# 85veegashield_v2.net
KiCad netlist of a schematic drawn in EAGLE
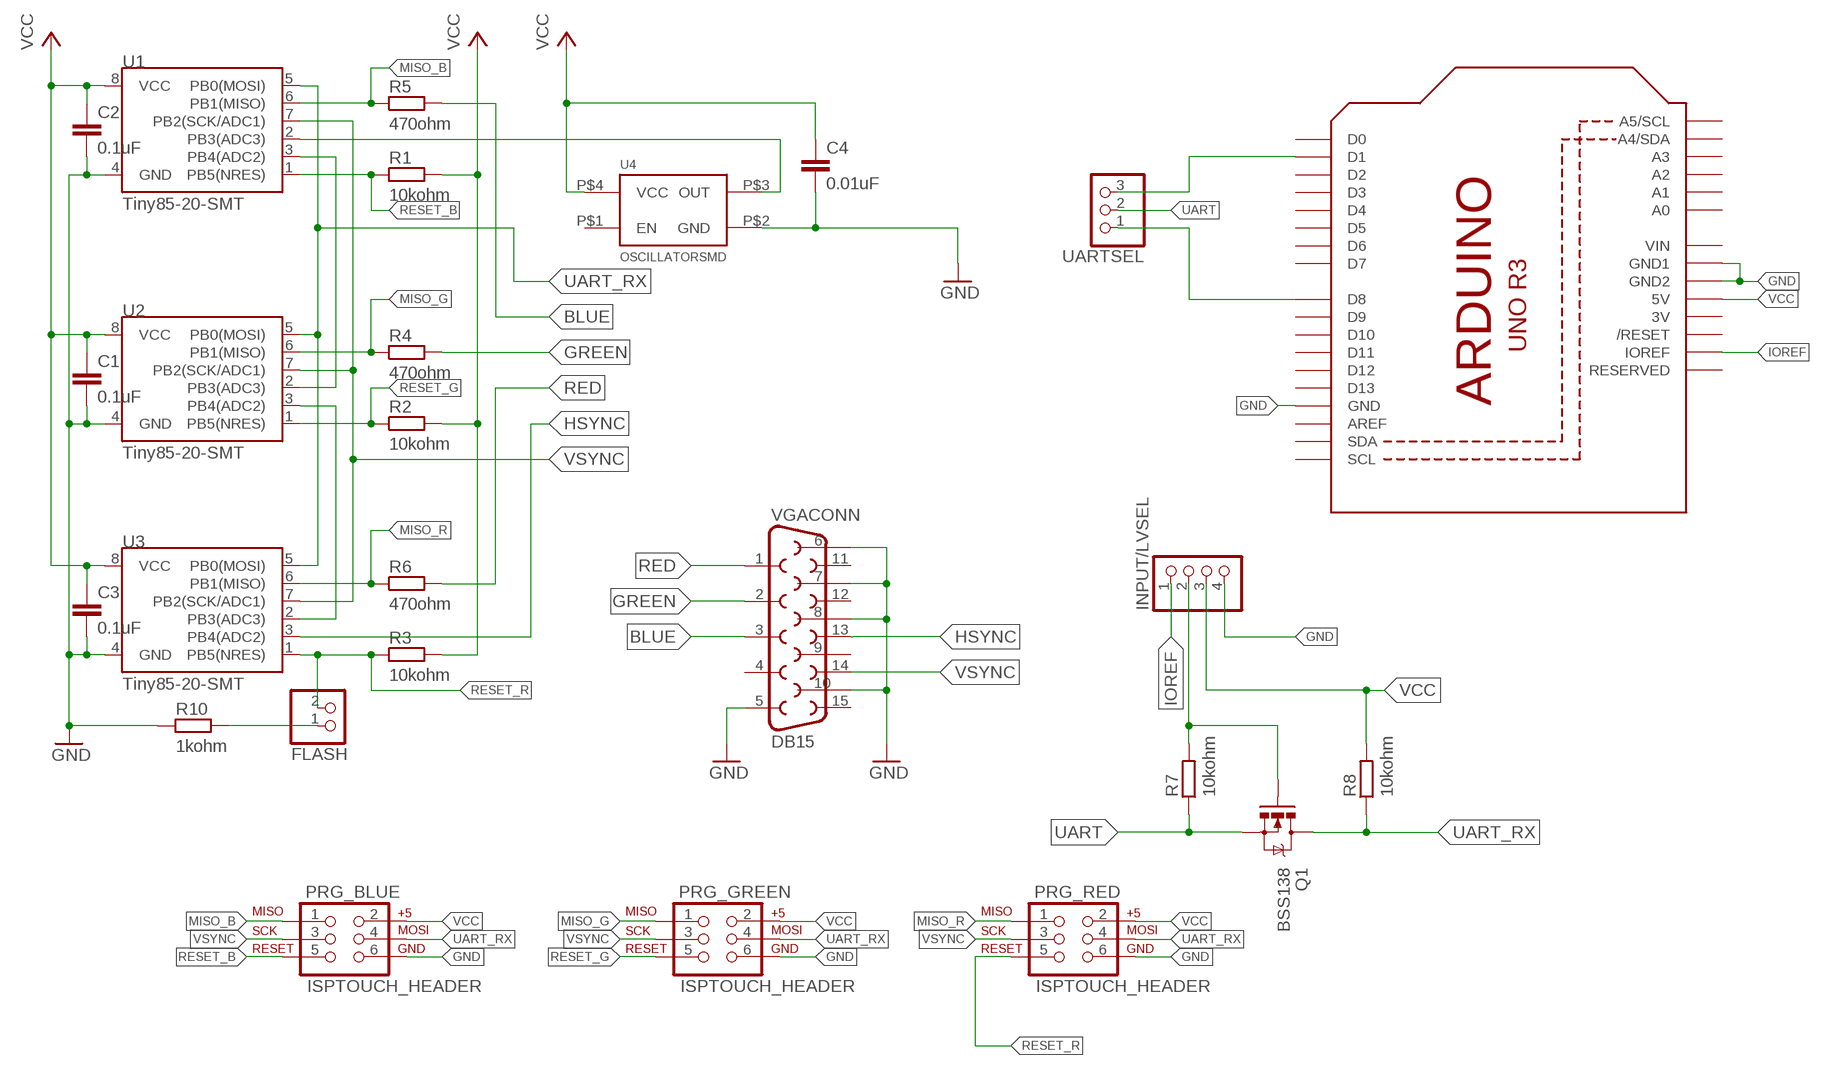
[diagram p0: schematic, sheet 1]

(export (version "E")
  (design (tool "Eeschema 10.0.6"))
  (components
    (comp (ref "C1")
      (value "0.1uF")
      (footprint "eagle-import:0603-CAP")
      (libsource (lib "eagle-import") (part "CAP0603-CAP"))
    )
    (comp (ref "C2")
      (value "0.1uF")
      (footprint "eagle-import:0603-CAP")
      (libsource (lib "eagle-import") (part "CAP0603-CAP"))
    )
    (comp (ref "C3")
      (value "0.1uF")
      (footprint "eagle-import:0603-CAP")
      (libsource (lib "eagle-import") (part "CAP0603-CAP"))
    )
    (comp (ref "C4")
      (value "0.01uF")
      (footprint "eagle-import:0603-CAP")
      (libsource (lib "eagle-import") (part "CAP0603-CAP"))
    )
    (comp (ref "FLASH")
      (value "PINHD-1X02_2.54-S")
      (footprint "eagle-import:1X02-S")
      (libsource (lib "eagle-import") (part "PINHD-1X02_2.54-S"))
    )
    (comp (ref "INPUT/LVSEL")
      (value "PINHD-1X04_2.54-S")
      (footprint "eagle-import:1X04-S")
      (libsource (lib "eagle-import") (part "PINHD-1X04_2.54-S"))
    )
    (comp (ref "PRG_BLUE")
      (value "ISPTOUCH_HEADER")
      (footprint "eagle-import:AVX_9188_6-WAY_MATING_GUIDE")
      (libsource (lib "eagle-import") (part "ISPTOUCH_HEADER"))
    )
    (comp (ref "PRG_GREEN")
      (value "ISPTOUCH_HEADER")
      (footprint "eagle-import:AVX_9188_6-WAY_MATING_GUIDE")
      (libsource (lib "eagle-import") (part "ISPTOUCH_HEADER"))
    )
    (comp (ref "PRG_RED")
      (value "ISPTOUCH_HEADER")
      (footprint "eagle-import:AVX_9188_6-WAY_MATING_GUIDE")
      (libsource (lib "eagle-import") (part "ISPTOUCH_HEADER"))
    )
    (comp (ref "Q1")
      (value "BSS138")
      (footprint "eagle-import:SOT23")
      (libsource (lib "eagle-import") (part "MOSFET-NCHANNELBSS138"))
    )
    (comp (ref "R1")
      (value "10kohm")
      (footprint "eagle-import:R0603")
      (libsource (lib "eagle-import") (part "RESISTOR"))
    )
    (comp (ref "R2")
      (value "10kohm")
      (footprint "eagle-import:R0603")
      (libsource (lib "eagle-import") (part "RESISTOR"))
    )
    (comp (ref "R3")
      (value "10kohm")
      (footprint "eagle-import:R0603")
      (libsource (lib "eagle-import") (part "RESISTOR"))
    )
    (comp (ref "R4")
      (value "470ohm")
      (footprint "eagle-import:R0603")
      (libsource (lib "eagle-import") (part "RESISTOR"))
    )
    (comp (ref "R5")
      (value "470ohm")
      (footprint "eagle-import:R0603")
      (libsource (lib "eagle-import") (part "RESISTOR"))
    )
    (comp (ref "R6")
      (value "470ohm")
      (footprint "eagle-import:R0603")
      (libsource (lib "eagle-import") (part "RESISTOR"))
    )
    (comp (ref "R7")
      (value "10kohm")
      (footprint "eagle-import:R0603")
      (libsource (lib "eagle-import") (part "RESISTOR"))
    )
    (comp (ref "R8")
      (value "10kohm")
      (footprint "eagle-import:R0603")
      (libsource (lib "eagle-import") (part "RESISTOR"))
    )
    (comp (ref "R10")
      (value "1kohm")
      (footprint "eagle-import:R0603")
      (libsource (lib "eagle-import") (part "RESISTOR"))
    )
    (comp (ref "U$1")
      (value "ARDUINOR3-DIMENSION")
      (footprint "eagle-import:ARDUINOR3")
      (libsource (lib "eagle-import") (part "ARDUINOR3-DIMENSION"))
    )
    (comp (ref "U1")
      (value "Tiny85-20-SMT")
      (footprint "eagle-import:SO08-EIAJ")
      (libsource (lib "eagle-import") (part "ATTINY45TINY85-20-SMT"))
    )
    (comp (ref "U2")
      (value "Tiny85-20-SMT")
      (footprint "eagle-import:SO08-EIAJ")
      (libsource (lib "eagle-import") (part "ATTINY45TINY85-20-SMT"))
    )
    (comp (ref "U3")
      (value "Tiny85-20-SMT")
      (footprint "eagle-import:SO08-EIAJ")
      (libsource (lib "eagle-import") (part "ATTINY45TINY85-20-SMT"))
    )
    (comp (ref "U4")
      (value "OSCILLATORSMD")
      (footprint "eagle-import:CRYSTAL-SMD-7X5")
      (libsource (lib "eagle-import") (part "OSCILLATORSMD"))
    )
    (comp (ref "UARTSEL")
      (value "PINHD-1X03_2.54-S")
      (footprint "eagle-import:1X03-S")
      (libsource (lib "eagle-import") (part "PINHD-1X03_2.54-S"))
    )
    (comp (ref "VGACONN")
      (value "DB15")
      (footprint "eagle-import:DB15")
      (libsource (lib "eagle-import") (part "DB15"))
    )
  )
  (nets
    (net (code "1") (name "/3V") (class "Default")
      (node (ref "U$1") (pin "3V") (pinfunction "3V_3V") (pintype "power_in"))
    )
    (net (code "2") (name "/VIN") (class "Default")
      (node (ref "U$1") (pin "VIN") (pinfunction "VIN_VIN") (pintype "power_in"))
    )
    (net (code "3") (name "BLUE") (class "Default")
      (node (ref "R5") (pin "2") (pinfunction "2_2") (pintype "passive"))
      (node (ref "VGACONN") (pin "3") (pinfunction "3_3") (pintype "passive"))
    )
    (net (code "4") (name "GND") (class "Default")
      (node (ref "C1") (pin "2") (pinfunction "2_2") (pintype "passive"))
      (node (ref "C2") (pin "2") (pinfunction "2_2") (pintype "passive"))
      (node (ref "C3") (pin "2") (pinfunction "2_2") (pintype "passive"))
      (node (ref "C4") (pin "2") (pinfunction "2_2") (pintype "passive"))
      (node (ref "INPUT/LVSEL") (pin "4") (pinfunction "4_4") (pintype "passive"))
      (node (ref "PRG_BLUE") (pin "6") (pinfunction "6_6") (pintype "passive"))
      (node (ref "PRG_GREEN") (pin "6") (pinfunction "6_6") (pintype "passive"))
      (node (ref "PRG_RED") (pin "6") (pinfunction "6_6") (pintype "passive"))
      (node (ref "R10") (pin "1") (pinfunction "1_1") (pintype "passive"))
      (node (ref "U$1") (pin "GND") (pinfunction "GND_GND") (pintype "power_in"))
      (node (ref "U$1") (pin "GND1") (pinfunction "GND1_GND1") (pintype "power_in"))
      (node (ref "U$1") (pin "GND2") (pinfunction "GND2_GND2") (pintype "power_in"))
      (node (ref "U1") (pin "4") (pinfunction "GND_4") (pintype "bidirectional"))
      (node (ref "U2") (pin "4") (pinfunction "GND_4") (pintype "bidirectional"))
      (node (ref "U3") (pin "4") (pinfunction "GND_4") (pintype "bidirectional"))
      (node (ref "U4") (pin "P$2") (pinfunction "GND_P$2") (pintype "bidirectional"))
      (node (ref "VGACONN") (pin "10") (pinfunction "10_10") (pintype "passive"))
      (node (ref "VGACONN") (pin "5") (pinfunction "5_5") (pintype "passive"))
      (node (ref "VGACONN") (pin "6") (pinfunction "6_6") (pintype "passive"))
      (node (ref "VGACONN") (pin "7") (pinfunction "7_7") (pintype "passive"))
      (node (ref "VGACONN") (pin "8") (pinfunction "8_8") (pintype "passive"))
    )
    (net (code "5") (name "GREEN") (class "Default")
      (node (ref "R4") (pin "2") (pinfunction "2_2") (pintype "passive"))
      (node (ref "VGACONN") (pin "2") (pinfunction "2_2") (pintype "passive"))
    )
    (net (code "6") (name "HSYNC") (class "Default")
      (node (ref "U3") (pin "3") (pinfunction "PB4(ADC2)_3") (pintype "bidirectional"))
      (node (ref "VGACONN") (pin "13") (pinfunction "13_13") (pintype "passive"))
    )
    (net (code "7") (name "IOREF") (class "Default")
      (node (ref "INPUT/LVSEL") (pin "1") (pinfunction "1_1") (pintype "passive"))
      (node (ref "U$1") (pin "IOREF") (pinfunction "IOREF_IOREF") (pintype "output"))
    )
    (net (code "8") (name "MISO_B") (class "Default")
      (node (ref "PRG_BLUE") (pin "1") (pinfunction "1_1") (pintype "passive"))
      (node (ref "R5") (pin "1") (pinfunction "1_1") (pintype "passive"))
      (node (ref "U1") (pin "6") (pinfunction "PB1(MISO)_6") (pintype "bidirectional"))
    )
    (net (code "9") (name "MISO_G") (class "Default")
      (node (ref "PRG_GREEN") (pin "1") (pinfunction "1_1") (pintype "passive"))
      (node (ref "R4") (pin "1") (pinfunction "1_1") (pintype "passive"))
      (node (ref "U2") (pin "6") (pinfunction "PB1(MISO)_6") (pintype "bidirectional"))
    )
    (net (code "10") (name "MISO_R") (class "Default")
      (node (ref "PRG_RED") (pin "1") (pinfunction "1_1") (pintype "passive"))
      (node (ref "R6") (pin "1") (pinfunction "1_1") (pintype "passive"))
      (node (ref "U3") (pin "6") (pinfunction "PB1(MISO)_6") (pintype "bidirectional"))
    )
    (net (code "11") (name "Net-(FLASH-Pad1)") (class "Default")
      (node (ref "FLASH") (pin "1") (pinfunction "1_1") (pintype "passive"))
      (node (ref "R10") (pin "2") (pinfunction "2_2") (pintype "passive"))
    )
    (net (code "12") (name "Net-(Q1-G)") (class "Default")
      (node (ref "INPUT/LVSEL") (pin "2") (pinfunction "2_2") (pintype "passive"))
      (node (ref "Q1") (pin "1") (pinfunction "G_1") (pintype "passive"))
      (node (ref "R7") (pin "2") (pinfunction "2_2") (pintype "passive"))
    )
    (net (code "13") (name "Net-(U$1-PadD1)") (class "Default")
      (node (ref "U$1") (pin "D1") (pinfunction "D1_D1") (pintype "bidirectional"))
      (node (ref "UARTSEL") (pin "3") (pinfunction "3_3") (pintype "passive"))
    )
    (net (code "14") (name "Net-(U$1-PadD8)") (class "Default")
      (node (ref "U$1") (pin "D8") (pinfunction "D8_D8") (pintype "bidirectional"))
      (node (ref "UARTSEL") (pin "1") (pinfunction "1_1") (pintype "passive"))
    )
    (net (code "15") (name "Net-(U1-PB3(ADC3))") (class "Default")
      (node (ref "U1") (pin "2") (pinfunction "PB3(ADC3)_2") (pintype "bidirectional"))
      (node (ref "U4") (pin "P$3") (pinfunction "OUT_P$3") (pintype "bidirectional"))
    )
    (net (code "16") (name "Net-(U1-PB4(ADC2))") (class "Default")
      (node (ref "U1") (pin "3") (pinfunction "PB4(ADC2)_3") (pintype "bidirectional"))
      (node (ref "U2") (pin "2") (pinfunction "PB3(ADC3)_2") (pintype "bidirectional"))
    )
    (net (code "17") (name "Net-(U2-PB4(ADC2))") (class "Default")
      (node (ref "U2") (pin "3") (pinfunction "PB4(ADC2)_3") (pintype "bidirectional"))
      (node (ref "U3") (pin "2") (pinfunction "PB3(ADC3)_2") (pintype "bidirectional"))
    )
    (net (code "18") (name "RED") (class "Default")
      (node (ref "R6") (pin "2") (pinfunction "2_2") (pintype "passive"))
      (node (ref "VGACONN") (pin "1") (pinfunction "1_1") (pintype "passive"))
    )
    (net (code "19") (name "RESET_B") (class "Default")
      (node (ref "PRG_BLUE") (pin "5") (pinfunction "5_5") (pintype "passive"))
      (node (ref "R1") (pin "1") (pinfunction "1_1") (pintype "passive"))
      (node (ref "U1") (pin "1") (pinfunction "PB5(NRES)_1") (pintype "bidirectional"))
    )
    (net (code "20") (name "RESET_G") (class "Default")
      (node (ref "PRG_GREEN") (pin "5") (pinfunction "5_5") (pintype "passive"))
      (node (ref "R2") (pin "1") (pinfunction "1_1") (pintype "passive"))
      (node (ref "U2") (pin "1") (pinfunction "PB5(NRES)_1") (pintype "bidirectional"))
    )
    (net (code "21") (name "RESET_R") (class "Default")
      (node (ref "FLASH") (pin "2") (pinfunction "2_2") (pintype "passive"))
      (node (ref "PRG_RED") (pin "5") (pinfunction "5_5") (pintype "passive"))
      (node (ref "R3") (pin "1") (pinfunction "1_1") (pintype "passive"))
      (node (ref "U3") (pin "1") (pinfunction "PB5(NRES)_1") (pintype "bidirectional"))
    )
    (net (code "22") (name "UART") (class "Default")
      (node (ref "Q1") (pin "2") (pinfunction "S_2") (pintype "passive"))
      (node (ref "R7") (pin "1") (pinfunction "1_1") (pintype "passive"))
      (node (ref "UARTSEL") (pin "2") (pinfunction "2_2") (pintype "passive"))
    )
    (net (code "23") (name "UART_RX") (class "Default")
      (node (ref "PRG_BLUE") (pin "4") (pinfunction "4_4") (pintype "passive"))
      (node (ref "PRG_GREEN") (pin "4") (pinfunction "4_4") (pintype "passive"))
      (node (ref "PRG_RED") (pin "4") (pinfunction "4_4") (pintype "passive"))
      (node (ref "Q1") (pin "3") (pinfunction "D_3") (pintype "passive"))
      (node (ref "R8") (pin "1") (pinfunction "1_1") (pintype "passive"))
      (node (ref "U1") (pin "5") (pinfunction "PB0(MOSI)_5") (pintype "bidirectional"))
      (node (ref "U2") (pin "5") (pinfunction "PB0(MOSI)_5") (pintype "bidirectional"))
      (node (ref "U3") (pin "5") (pinfunction "PB0(MOSI)_5") (pintype "bidirectional"))
    )
    (net (code "24") (name "VCC") (class "Default")
      (node (ref "C1") (pin "1") (pinfunction "1_1") (pintype "passive"))
      (node (ref "C2") (pin "1") (pinfunction "1_1") (pintype "passive"))
      (node (ref "C3") (pin "1") (pinfunction "1_1") (pintype "passive"))
      (node (ref "C4") (pin "1") (pinfunction "1_1") (pintype "passive"))
      (node (ref "INPUT/LVSEL") (pin "3") (pinfunction "3_3") (pintype "passive"))
      (node (ref "PRG_BLUE") (pin "2") (pinfunction "2_2") (pintype "passive"))
      (node (ref "PRG_GREEN") (pin "2") (pinfunction "2_2") (pintype "passive"))
      (node (ref "PRG_RED") (pin "2") (pinfunction "2_2") (pintype "passive"))
      (node (ref "R1") (pin "2") (pinfunction "2_2") (pintype "passive"))
      (node (ref "R2") (pin "2") (pinfunction "2_2") (pintype "passive"))
      (node (ref "R3") (pin "2") (pinfunction "2_2") (pintype "passive"))
      (node (ref "R8") (pin "2") (pinfunction "2_2") (pintype "passive"))
      (node (ref "U$1") (pin "5V") (pinfunction "5V_5V") (pintype "power_in"))
      (node (ref "U1") (pin "8") (pinfunction "VCC_8") (pintype "bidirectional"))
      (node (ref "U2") (pin "8") (pinfunction "VCC_8") (pintype "bidirectional"))
      (node (ref "U3") (pin "8") (pinfunction "VCC_8") (pintype "bidirectional"))
      (node (ref "U4") (pin "P$4") (pinfunction "VCC_P$4") (pintype "bidirectional"))
    )
    (net (code "25") (name "VSYNC") (class "Default")
      (node (ref "PRG_BLUE") (pin "3") (pinfunction "3_3") (pintype "passive"))
      (node (ref "PRG_GREEN") (pin "3") (pinfunction "3_3") (pintype "passive"))
      (node (ref "PRG_RED") (pin "3") (pinfunction "3_3") (pintype "passive"))
      (node (ref "U1") (pin "7") (pinfunction "PB2(SCK/ADC1)_7") (pintype "bidirectional"))
      (node (ref "U2") (pin "7") (pinfunction "PB2(SCK/ADC1)_7") (pintype "bidirectional"))
      (node (ref "U3") (pin "7") (pinfunction "PB2(SCK/ADC1)_7") (pintype "bidirectional"))
      (node (ref "VGACONN") (pin "14") (pinfunction "14_14") (pintype "passive"))
    )
    (net (code "26") (name "unconnected-(U$1-A4{slash}SDA-PadA4)") (class "Default")
      (node (ref "U$1") (pin "A4") (pinfunction "A4/SDA_A4") (pintype "bidirectional"))
    )
    (net (code "27") (name "unconnected-(U$1-A5{slash}SCL-PadA5)") (class "Default")
      (node (ref "U$1") (pin "A5") (pinfunction "A5/SCL_A5") (pintype "bidirectional"))
    )
    (net (code "28") (name "unconnected-(U$1-PadA0)") (class "Default")
      (node (ref "U$1") (pin "A0") (pinfunction "A0_A0") (pintype "bidirectional"))
    )
    (net (code "29") (name "unconnected-(U$1-PadA1)") (class "Default")
      (node (ref "U$1") (pin "A1") (pinfunction "A1_A1") (pintype "bidirectional"))
    )
    (net (code "30") (name "unconnected-(U$1-PadA2)") (class "Default")
      (node (ref "U$1") (pin "A2") (pinfunction "A2_A2") (pintype "bidirectional"))
    )
    (net (code "31") (name "unconnected-(U$1-PadA3)") (class "Default")
      (node (ref "U$1") (pin "A3") (pinfunction "A3_A3") (pintype "bidirectional"))
    )
    (net (code "32") (name "unconnected-(U$1-PadAREF)") (class "Default")
      (node (ref "U$1") (pin "AREF") (pinfunction "AREF_AREF") (pintype "bidirectional"))
    )
    (net (code "33") (name "unconnected-(U$1-PadD0)") (class "Default")
      (node (ref "U$1") (pin "D0") (pinfunction "D0_D0") (pintype "bidirectional"))
    )
    (net (code "34") (name "unconnected-(U$1-PadD2)") (class "Default")
      (node (ref "U$1") (pin "D2") (pinfunction "D2_D2") (pintype "bidirectional"))
    )
    (net (code "35") (name "unconnected-(U$1-PadD3)") (class "Default")
      (node (ref "U$1") (pin "D3") (pinfunction "D3_D3") (pintype "bidirectional"))
    )
    (net (code "36") (name "unconnected-(U$1-PadD4)") (class "Default")
      (node (ref "U$1") (pin "D4") (pinfunction "D4_D4") (pintype "bidirectional"))
    )
    (net (code "37") (name "unconnected-(U$1-PadD5)") (class "Default")
      (node (ref "U$1") (pin "D5") (pinfunction "D5_D5") (pintype "bidirectional"))
    )
    (net (code "38") (name "unconnected-(U$1-PadD6)") (class "Default")
      (node (ref "U$1") (pin "D6") (pinfunction "D6_D6") (pintype "bidirectional"))
    )
    (net (code "39") (name "unconnected-(U$1-PadD7)") (class "Default")
      (node (ref "U$1") (pin "D7") (pinfunction "D7_D7") (pintype "bidirectional"))
    )
    (net (code "40") (name "unconnected-(U$1-PadD9)") (class "Default")
      (node (ref "U$1") (pin "D9") (pinfunction "D9_D9") (pintype "bidirectional"))
    )
    (net (code "41") (name "unconnected-(U$1-PadD10)") (class "Default")
      (node (ref "U$1") (pin "D10") (pinfunction "D10_D10") (pintype "bidirectional"))
    )
    (net (code "42") (name "unconnected-(U$1-PadD11)") (class "Default")
      (node (ref "U$1") (pin "D11") (pinfunction "D11_D11") (pintype "bidirectional"))
    )
    (net (code "43") (name "unconnected-(U$1-PadD12)") (class "Default")
      (node (ref "U$1") (pin "D12") (pinfunction "D12_D12") (pintype "bidirectional"))
    )
    (net (code "44") (name "unconnected-(U$1-PadD13)") (class "Default")
      (node (ref "U$1") (pin "D13") (pinfunction "D13_D13") (pintype "bidirectional"))
    )
    (net (code "45") (name "unconnected-(U$1-PadRESERVED)") (class "Default")
      (node (ref "U$1") (pin "RESERVED") (pinfunction "RESERVED_RESERVED") (pintype "no_connect"))
    )
    (net (code "46") (name "unconnected-(U$1-PadSCL)") (class "Default")
      (node (ref "U$1") (pin "SCL") (pinfunction "SCL_SCL") (pintype "bidirectional"))
    )
    (net (code "47") (name "unconnected-(U$1-PadSDA)") (class "Default")
      (node (ref "U$1") (pin "SDA") (pinfunction "SDA_SDA") (pintype "bidirectional"))
    )
    (net (code "48") (name "unconnected-(U$1-{slash}RESET-PadRESET)") (class "Default")
      (node (ref "U$1") (pin "RESET") (pinfunction "/RESET_RESET") (pintype "bidirectional"))
    )
    (net (code "49") (name "unconnected-(U4-EN-PadP$1)") (class "Default")
      (node (ref "U4") (pin "P$1") (pinfunction "EN_P$1") (pintype "bidirectional"))
    )
    (net (code "50") (name "unconnected-(VGACONN-Pad4)") (class "Default")
      (node (ref "VGACONN") (pin "4") (pinfunction "4_4") (pintype "passive"))
    )
    (net (code "51") (name "unconnected-(VGACONN-Pad9)") (class "Default")
      (node (ref "VGACONN") (pin "9") (pinfunction "9_9") (pintype "passive"))
    )
    (net (code "52") (name "unconnected-(VGACONN-Pad11)") (class "Default")
      (node (ref "VGACONN") (pin "11") (pinfunction "11_11") (pintype "passive"))
    )
    (net (code "53") (name "unconnected-(VGACONN-Pad12)") (class "Default")
      (node (ref "VGACONN") (pin "12") (pinfunction "12_12") (pintype "passive"))
    )
    (net (code "54") (name "unconnected-(VGACONN-Pad15)") (class "Default")
      (node (ref "VGACONN") (pin "15") (pinfunction "15_15") (pintype "passive"))
    )
  )
)
